# DIGITAL.net
KiCad netlist of a schematic drawn in Altium Designer
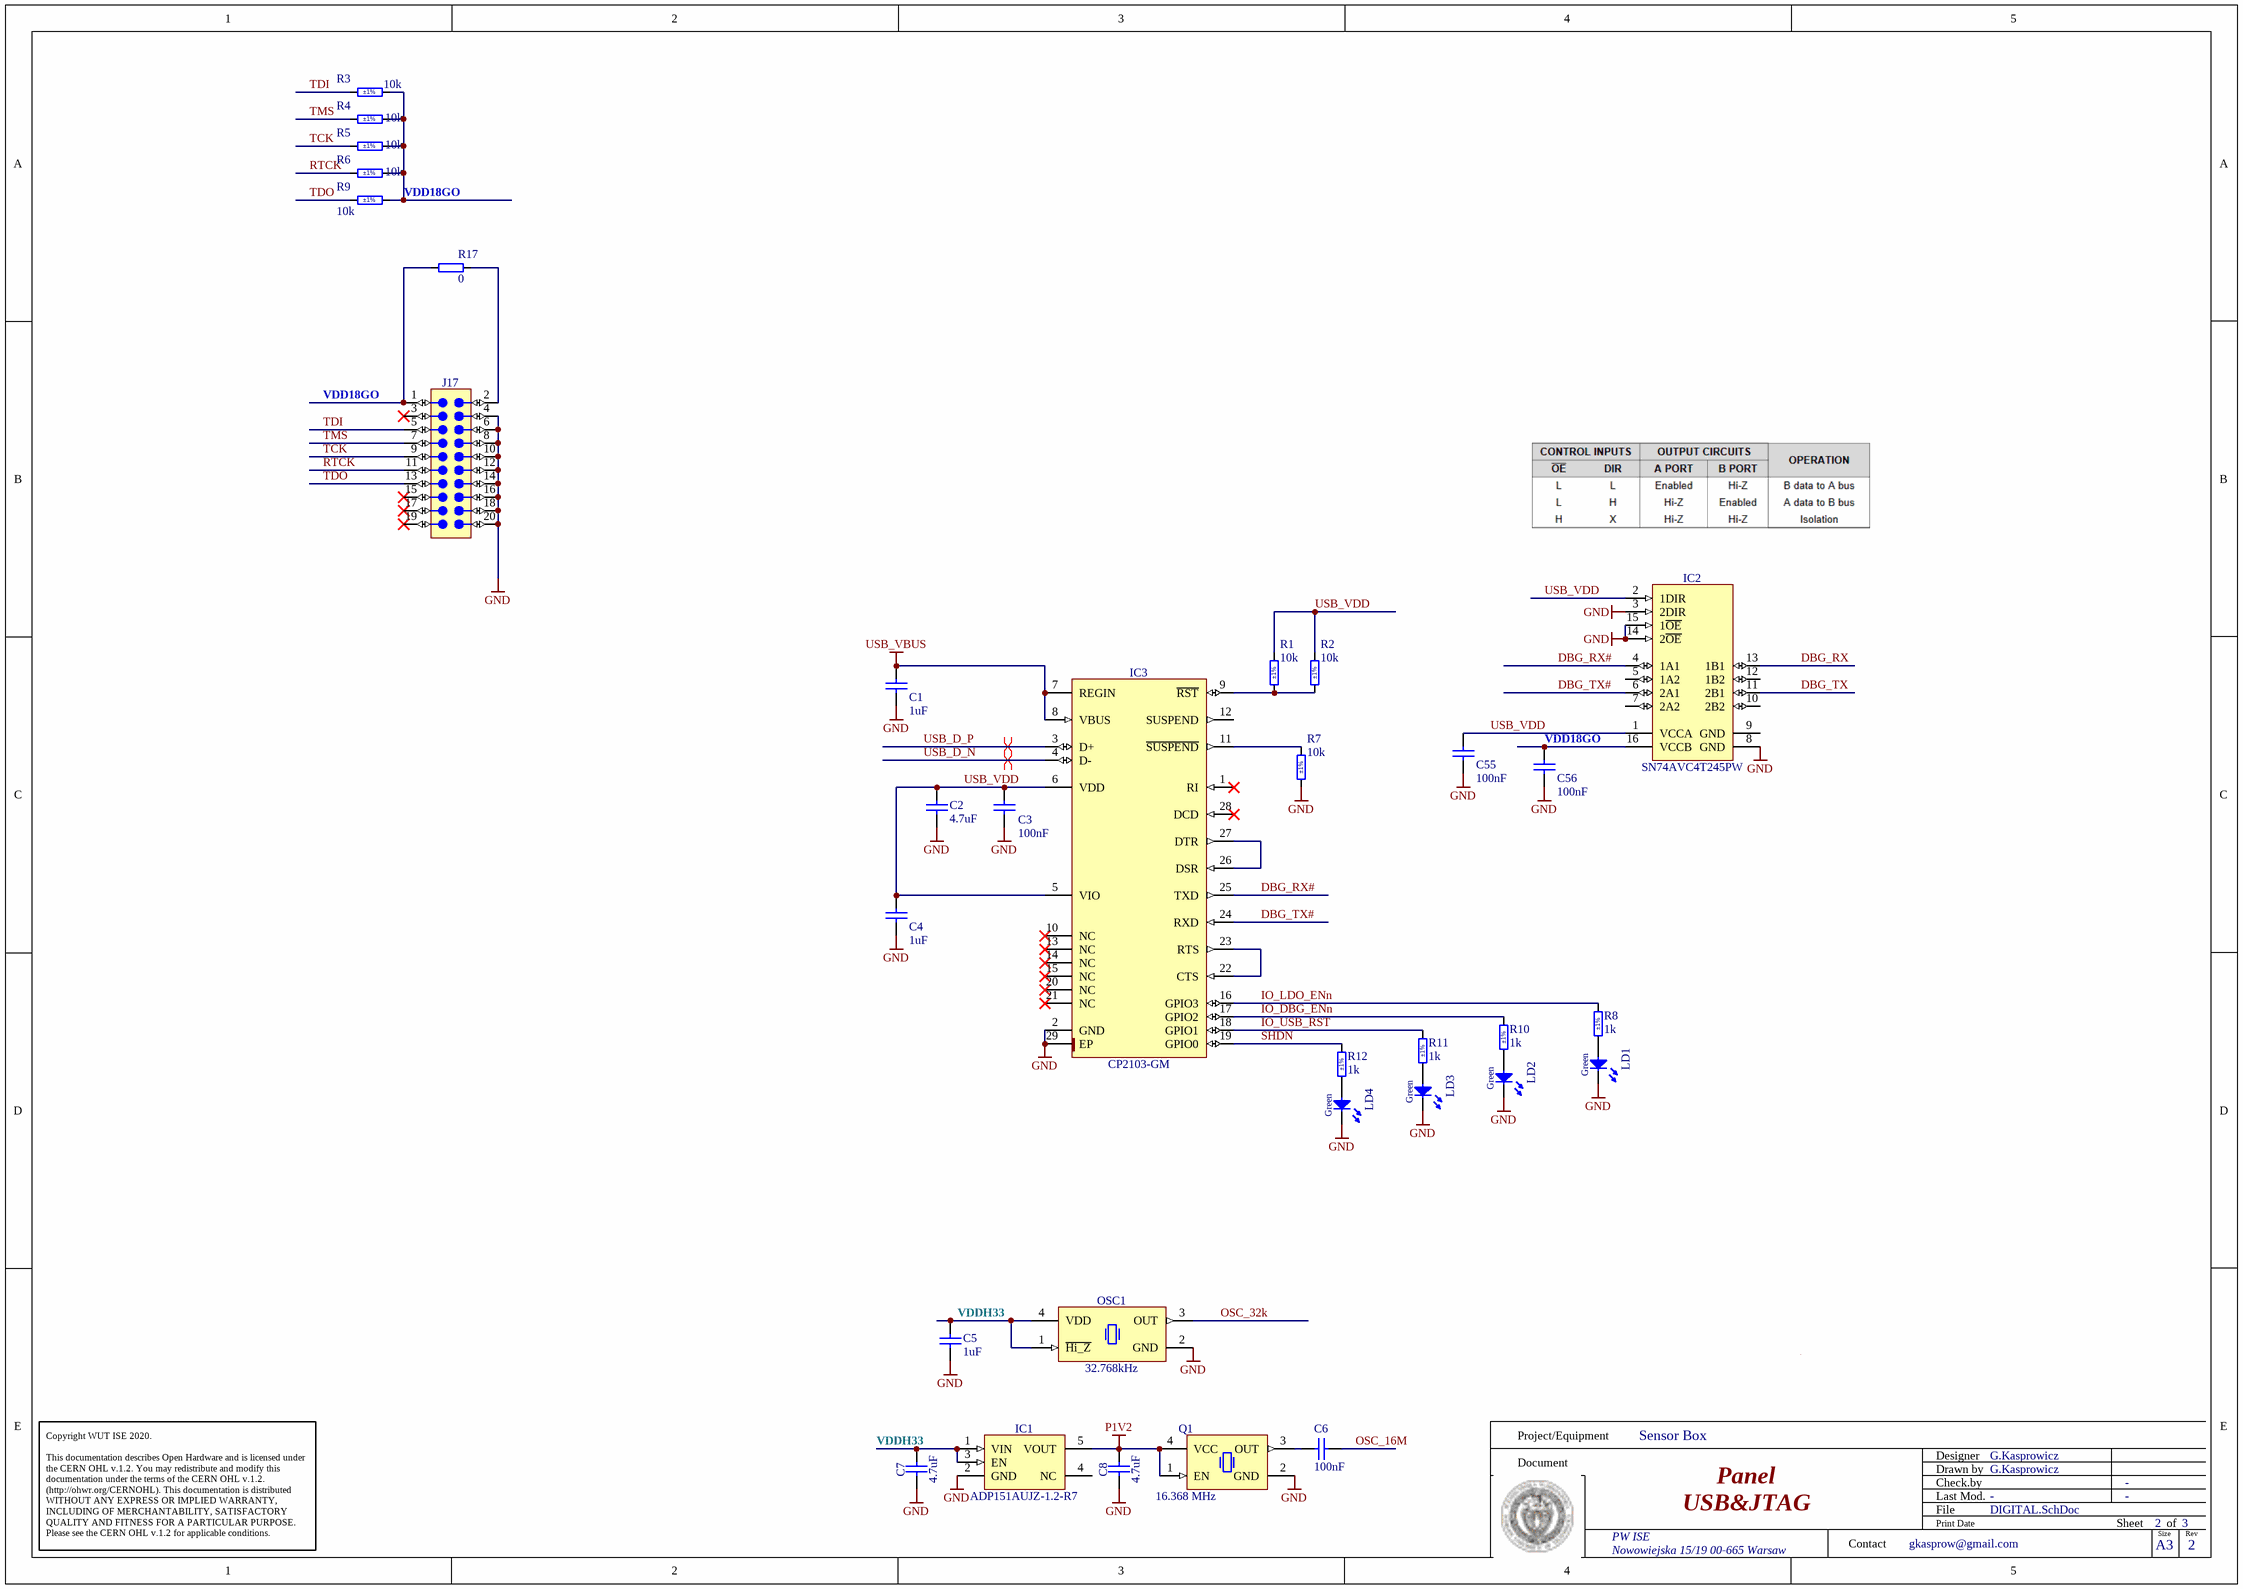
[diagram p0: DIGITAL.SchDoc]

(export (version "E")
  (design (tool "Eeschema 10.0.6"))
  (components
    (comp (ref "C1")
      (value "1uF")
      (footprint "CAPC1005X55N")
      (description "Non-polarised capacitor")
      (fields
        (field (name "PART NUMBER") "CC0402_1UF_16V_10%_X5R")
        (field (name "VOLTAGE") "16V")
        (field (name "AUTHOR") "CERN DEM JLC")
      )
      (libsource (lib "Capacitors") (part "Capacitor - non polarized"))
    )
    (comp (ref "C2")
      (value "4.7uF")
      (footprint "CAPC1005X55N")
      (description "Non-polarised capacitor")
      (fields
        (field (name "PART NUMBER") "CC0402_4.7UF_10V_10%_X5R")
        (field (name "VOLTAGE") "10V")
        (field (name "AUTHOR") "CERN DEM BC")
      )
      (libsource (lib "Capacitors") (part "Capacitor - non polarized"))
    )
    (comp (ref "C3")
      (value "100nF")
      (footprint "CAPC1005X55N")
      (description "Non-polarised capacitor")
      (fields
        (field (name "PART NUMBER") "CC0402_100NF_16V_10%_X5R")
        (field (name "VOLTAGE") "16V")
        (field (name "AUTHOR") "CERN DEM JLC")
      )
      (libsource (lib "Capacitors") (part "Capacitor - non polarized"))
    )
    (comp (ref "C4")
      (value "1uF")
      (footprint "CAPC1005X55N")
      (description "Non-polarised capacitor")
      (fields
        (field (name "PART NUMBER") "CC0402_1UF_16V_10%_X5R")
        (field (name "VOLTAGE") "16V")
        (field (name "AUTHOR") "CERN DEM JLC")
      )
      (libsource (lib "Capacitors") (part "Capacitor - non polarized"))
    )
    (comp (ref "C5")
      (value "1uF")
      (footprint "CAPC1005X55N")
      (description "Non-polarised capacitor")
      (fields
        (field (name "PART NUMBER") "CC0402_1UF_16V_10%_X5R")
        (field (name "VOLTAGE") "16V")
        (field (name "AUTHOR") "CERN DEM JLC")
      )
      (libsource (lib "Capacitors") (part "Capacitor - non polarized"))
    )
    (comp (ref "C6")
      (value "100nF")
      (footprint "CAPC1005X55N")
      (description "Non-polarised capacitor")
      (fields
        (field (name "PART NUMBER") "CC0402_100NF_16V_10%_X5R")
        (field (name "VOLTAGE") "16V")
        (field (name "AUTHOR") "CERN DEM JLC")
      )
      (libsource (lib "Capacitors") (part "Capacitor - non polarized"))
    )
    (comp (ref "C7")
      (value "4.7uF")
      (footprint "CAPC1005X55N")
      (description "Non-polarised capacitor")
      (fields
        (field (name "PART NUMBER") "CC0402_4.7UF_10V_10%_X5R")
        (field (name "VOLTAGE") "10V")
        (field (name "AUTHOR") "CERN DEM BC")
      )
      (libsource (lib "Capacitors") (part "Capacitor - non polarized"))
    )
    (comp (ref "C8")
      (value "4.7uF")
      (footprint "CAPC1005X55N")
      (description "Non-polarised capacitor")
      (fields
        (field (name "PART NUMBER") "CC0402_4.7UF_10V_10%_X5R")
        (field (name "VOLTAGE") "10V")
        (field (name "AUTHOR") "CERN DEM BC")
      )
      (libsource (lib "Capacitors") (part "Capacitor - non polarized"))
    )
    (comp (ref "C55")
      (value "100nF")
      (footprint "CAPC1005X55N")
      (description "Non-polarised capacitor")
      (fields
        (field (name "PART NUMBER") "CC0402_100NF_16V_10%_X5R")
        (field (name "VOLTAGE") "16V")
        (field (name "AUTHOR") "CERN DEM JLC")
      )
      (libsource (lib "Capacitors") (part "Capacitor - non polarized"))
    )
    (comp (ref "C56")
      (value "100nF")
      (footprint "CAPC1005X55N")
      (description "Non-polarised capacitor")
      (fields
        (field (name "PART NUMBER") "CC0402_100NF_16V_10%_X5R")
        (field (name "VOLTAGE") "16V")
        (field (name "AUTHOR") "CERN DEM JLC")
      )
      (libsource (lib "Capacitors") (part "Capacitor - non polarized"))
    )
    (comp (ref "IC1")
      (value "ADP151AUJZ-1.2-R7")
      (footprint "SOT95P280X90-5N")
      (description "Ultralow Noise, 200 mA CMOS Linear Regulator")
      (fields (field (name "MANUFACTURER") "ANALOG DEVICES") (field (name "AUTHOR") "CERN DEM JLC"))
      (libsource (lib "ICs And Semiconductors") (part "ADP151AUJZ"))
    )
    (comp (ref "IC2")
      (value "SN74AVC4T245PW")
      (footprint "SOP65P640X120-16N")
      (description "4-Bit Dual-Supply Bus Transceiver with Configurable Voltage Translation and 3-State Output")
      (fields (field (name "MANUFACTURER") "TEXAS INSTRUMENTS") (field (name "AUTHOR") "CERN DEM JLC"))
      (libsource (lib "ICs And Semiconductors") (part "744T245"))
    )
    (comp (ref "IC3")
      (value "CP2103-GM")
      (footprint "QFN50P500X500X100-29N-S335")
      (description "Single-Chip USB to UART Bridge")
      (fields (field (name "MANUFACTURER") "SILICON LABS") (field (name "AUTHOR") "CERN DEM JLC"))
      (libsource (lib "ICs And Semiconductors") (part "CP2103-GM"))
    )
    (comp (ref "J17")
      (value "Header 20")
      (footprint "SAMTEC_MTLW-110-07-L-D-250")
      (description "Connector 20 Male")
      (fields
        (field (name "PART NUMBER") "SAMTEC_MTLW-110-07-L-D-250")
        (field (name "MANUFACTURER") "SAMTEC")
        (field (name "AUTHOR") "CERN DEM JLC")
      )
      (libsource (lib "Connectors") (part "Connector 20 Male"))
    )
    (comp (ref "LD1")
      (value "Green")
      (footprint "LED_KINGBRIGHT_KP-1608CGCK")
      (description "LED Green 1C 2A")
      (fields
        (field (name "PART NUMBER") "LED_KINGBRIGHT_KP-1608CGCK")
        (field (name "MANUFACTURER") "KINGBRIGHT")
        (field (name "AUTHOR") "CERN DEM HF")
      )
      (libsource (lib "ICs And Semiconductors") (part "LED Green 1C 2A"))
    )
    (comp (ref "LD2")
      (value "Green")
      (footprint "LED_KINGBRIGHT_KP-1608CGCK")
      (description "LED Green 1C 2A")
      (fields
        (field (name "PART NUMBER") "LED_KINGBRIGHT_KP-1608CGCK")
        (field (name "MANUFACTURER") "KINGBRIGHT")
        (field (name "AUTHOR") "CERN DEM HF")
      )
      (libsource (lib "ICs And Semiconductors") (part "LED Green 1C 2A"))
    )
    (comp (ref "LD3")
      (value "Green")
      (footprint "LED_KINGBRIGHT_KP-1608CGCK")
      (description "LED Green 1C 2A")
      (fields
        (field (name "PART NUMBER") "LED_KINGBRIGHT_KP-1608CGCK")
        (field (name "MANUFACTURER") "KINGBRIGHT")
        (field (name "AUTHOR") "CERN DEM HF")
      )
      (libsource (lib "ICs And Semiconductors") (part "LED Green 1C 2A"))
    )
    (comp (ref "LD4")
      (value "Green")
      (footprint "LED_KINGBRIGHT_KP-1608CGCK")
      (description "LED Green 1C 2A")
      (fields
        (field (name "PART NUMBER") "LED_KINGBRIGHT_KP-1608CGCK")
        (field (name "MANUFACTURER") "KINGBRIGHT")
        (field (name "AUTHOR") "CERN DEM HF")
      )
      (libsource (lib "ICs And Semiconductors") (part "LED Green 1C 2A"))
    )
    (comp (ref "OSC1")
      (value "32.768kHz")
      (footprint "OSC_ABRACON_ASE")
      (description "Oscillator 32.768KHZ 25PPM 3.3V 3.2 x 2.5 x 1.2mm")
      (fields
        (field (name "PART NUMBER") "OSC_32.768kHz_ABRACON_ASEK-32.768KHz-LRT")
        (field (name "MANUFACTURER") "ABRACON")
        (field (name "AUTHOR") "GK")
      )
      (libsource (lib "Crystals_Oscillators") (part "OSC_32.768kHz_ABRACON_ASEK-32.768KHz-LRT"))
    )
    (comp (ref "Q1")
      (value "16.368 MHz")
      (footprint "XTAL_TXC_8Y")
      (description "2.0 x 1.6mm SMD TCXO 16.368 MHz 0.5ppm 1.2V")
      (fields
        (field (name "PART NUMBER") "OSC_16.368 MHz _IQD_LFTCXO077226Cutt")
        (field (name "MANUFACTURER") "IQD")
        (field (name "AUTHOR") "GK")
      )
      (libsource (lib "Crystals_Oscillators") (part "OSC_16.368 MHz _IQD_LFTCXO077226Cutt"))
    )
    (comp (ref "R1")
      (value "10k")
      (footprint "RESC1005X40N")
      (description "Resistor - 1%")
      (fields
        (field (name "TOLERANCE") "±1%")
        (field (name "PART NUMBER") "R0402_10K_1%_0.0625W_100PPM")
        (field (name "POWER") "0.0625W")
        (field (name "AUTHOR") "CERN DEM JLC")
      )
      (libsource (lib "Resistors") (part "Resistor - 1%"))
    )
    (comp (ref "R2")
      (value "10k")
      (footprint "RESC1005X40N")
      (description "Resistor - 1%")
      (fields
        (field (name "TOLERANCE") "±1%")
        (field (name "PART NUMBER") "R0402_10K_1%_0.0625W_100PPM")
        (field (name "POWER") "0.0625W")
        (field (name "AUTHOR") "CERN DEM JLC")
      )
      (libsource (lib "Resistors") (part "Resistor - 1%"))
    )
    (comp (ref "R3")
      (value "10k")
      (footprint "RESC1005X40N")
      (description "Resistor - 1%")
      (fields
        (field (name "TOLERANCE") "±1%")
        (field (name "PART NUMBER") "R0402_10K_1%_0.0625W_100PPM")
        (field (name "POWER") "0.0625W")
        (field (name "AUTHOR") "CERN DEM JLC")
      )
      (libsource (lib "Resistors") (part "Resistor - 1%"))
    )
    (comp (ref "R4")
      (value "10k")
      (footprint "RESC1005X40N")
      (description "Resistor - 1%")
      (fields
        (field (name "TOLERANCE") "±1%")
        (field (name "PART NUMBER") "R0402_10K_1%_0.0625W_100PPM")
        (field (name "POWER") "0.0625W")
        (field (name "AUTHOR") "CERN DEM JLC")
      )
      (libsource (lib "Resistors") (part "Resistor - 1%"))
    )
    (comp (ref "R5")
      (value "10k")
      (footprint "RESC1005X40N")
      (description "Resistor - 1%")
      (fields
        (field (name "TOLERANCE") "±1%")
        (field (name "PART NUMBER") "R0402_10K_1%_0.0625W_100PPM")
        (field (name "POWER") "0.0625W")
        (field (name "AUTHOR") "CERN DEM JLC")
      )
      (libsource (lib "Resistors") (part "Resistor - 1%"))
    )
    (comp (ref "R6")
      (value "10k")
      (footprint "RESC1005X40N")
      (description "Resistor - 1%")
      (fields
        (field (name "TOLERANCE") "±1%")
        (field (name "PART NUMBER") "R0402_10K_1%_0.0625W_100PPM")
        (field (name "POWER") "0.0625W")
        (field (name "AUTHOR") "CERN DEM JLC")
      )
      (libsource (lib "Resistors") (part "Resistor - 1%"))
    )
    (comp (ref "R7")
      (value "10k")
      (footprint "RESC1005X40N")
      (description "Resistor - 1%")
      (fields
        (field (name "TOLERANCE") "±1%")
        (field (name "PART NUMBER") "R0402_10K_1%_0.0625W_100PPM")
        (field (name "POWER") "0.0625W")
        (field (name "AUTHOR") "CERN DEM JLC")
      )
      (libsource (lib "Resistors") (part "Resistor - 1%"))
    )
    (comp (ref "R8")
      (value "1k")
      (footprint "RESC1005X40N")
      (description "Resistor - 1%")
      (fields
        (field (name "TOLERANCE") "±1%")
        (field (name "PART NUMBER") "R0402_1K_1%_0.0625W_100PPM")
        (field (name "POWER") "0.0625W")
        (field (name "AUTHOR") "CERN DEM JLC")
      )
      (libsource (lib "Resistors") (part "Resistor - 1%"))
    )
    (comp (ref "R9")
      (value "10k")
      (footprint "RESC1005X40N")
      (description "Resistor - 1%")
      (fields
        (field (name "TOLERANCE") "±1%")
        (field (name "PART NUMBER") "R0402_10K_1%_0.0625W_100PPM")
        (field (name "POWER") "0.0625W")
        (field (name "AUTHOR") "CERN DEM JLC")
      )
      (libsource (lib "Resistors") (part "Resistor - 1%"))
    )
    (comp (ref "R10")
      (value "1k")
      (footprint "RESC1005X40N")
      (description "Resistor - 1%")
      (fields
        (field (name "TOLERANCE") "±1%")
        (field (name "PART NUMBER") "R0402_1K_1%_0.0625W_100PPM")
        (field (name "POWER") "0.0625W")
        (field (name "AUTHOR") "CERN DEM JLC")
      )
      (libsource (lib "Resistors") (part "Resistor - 1%"))
    )
    (comp (ref "R11")
      (value "1k")
      (footprint "RESC1005X40N")
      (description "Resistor - 1%")
      (fields
        (field (name "TOLERANCE") "±1%")
        (field (name "PART NUMBER") "R0402_1K_1%_0.0625W_100PPM")
        (field (name "POWER") "0.0625W")
        (field (name "AUTHOR") "CERN DEM JLC")
      )
      (libsource (lib "Resistors") (part "Resistor - 1%"))
    )
    (comp (ref "R12")
      (value "1k")
      (footprint "RESC1005X40N")
      (description "Resistor - 1%")
      (fields
        (field (name "TOLERANCE") "±1%")
        (field (name "PART NUMBER") "R0402_1K_1%_0.0625W_100PPM")
        (field (name "POWER") "0.0625W")
        (field (name "AUTHOR") "CERN DEM JLC")
      )
      (libsource (lib "Resistors") (part "Resistor - 1%"))
    )
    (comp (ref "R17")
      (value "0")
      (footprint "RESC1005X40N")
      (description "Resistor")
      (fields
        (field (name "PART NUMBER") "R0402_0R_JUMPER")
        (field (name "MANUFACTURER") "GENERIC")
        (field (name "AUTHOR") "CERN DEM JLC")
      )
      (libsource (lib "Resistors") (part "Resistor"))
    )
  )
  (nets
    (net (code "1") (name "/DBG_RX") (class "Default")
      (node (ref "IC2") (pin "13") (pinfunction "1B1_13") (pintype "bidirectional"))
    )
    (net (code "2") (name "/DBG_RX#") (class "Default")
      (node (ref "IC2") (pin "4") (pinfunction "1A1_4") (pintype "bidirectional"))
      (node (ref "IC3") (pin "25") (pinfunction "TXD_25") (pintype "output"))
    )
    (net (code "3") (name "/DBG_TX") (class "Default")
      (node (ref "IC2") (pin "11") (pinfunction "2B1_11") (pintype "bidirectional"))
    )
    (net (code "4") (name "/DBG_TX#") (class "Default")
      (node (ref "IC2") (pin "6") (pinfunction "2A1_6") (pintype "bidirectional"))
      (node (ref "IC3") (pin "24") (pinfunction "RXD_24") (pintype "input"))
    )
    (net (code "5") (name "/IO_DBG_ENn") (class "Default")
      (node (ref "IC3") (pin "17") (pinfunction "GPIO2_17") (pintype "bidirectional"))
      (node (ref "R10") (pin "2") (pinfunction "2_2") (pintype "passive"))
    )
    (net (code "6") (name "/IO_LDO_ENn") (class "Default")
      (node (ref "IC3") (pin "16") (pinfunction "GPIO3_16") (pintype "bidirectional"))
      (node (ref "R8") (pin "2") (pinfunction "2_2") (pintype "passive"))
    )
    (net (code "7") (name "/IO_USB_RST") (class "Default")
      (node (ref "IC3") (pin "18") (pinfunction "GPIO1_18") (pintype "bidirectional"))
      (node (ref "R11") (pin "2") (pinfunction "2_2") (pintype "passive"))
    )
    (net (code "8") (name "/OSC_16M") (class "Default")
      (node (ref "C6") (pin "2") (pinfunction "2_2") (pintype "passive"))
    )
    (net (code "9") (name "/OSC_32k") (class "Default")
      (node (ref "OSC1") (pin "3") (pinfunction "OUT_3") (pintype "output"))
    )
    (net (code "10") (name "/RTCK") (class "Default")
      (node (ref "J17") (pin "11") (pinfunction "11_11") (pintype "bidirectional"))
      (node (ref "R6") (pin "1") (pinfunction "1_1") (pintype "passive"))
    )
    (net (code "11") (name "/SHDN") (class "Default")
      (node (ref "IC3") (pin "19") (pinfunction "GPIO0_19") (pintype "bidirectional"))
      (node (ref "R12") (pin "2") (pinfunction "2_2") (pintype "passive"))
    )
    (net (code "12") (name "/TCK") (class "Default")
      (node (ref "J17") (pin "9") (pinfunction "9_9") (pintype "bidirectional"))
      (node (ref "R5") (pin "1") (pinfunction "1_1") (pintype "passive"))
    )
    (net (code "13") (name "/TDI") (class "Default")
      (node (ref "J17") (pin "5") (pinfunction "5_5") (pintype "bidirectional"))
      (node (ref "R3") (pin "1") (pinfunction "1_1") (pintype "passive"))
    )
    (net (code "14") (name "/TDO") (class "Default")
      (node (ref "J17") (pin "13") (pinfunction "13_13") (pintype "bidirectional"))
      (node (ref "R9") (pin "1") (pinfunction "1_1") (pintype "passive"))
    )
    (net (code "15") (name "/TMS") (class "Default")
      (node (ref "J17") (pin "7") (pinfunction "7_7") (pintype "bidirectional"))
      (node (ref "R4") (pin "1") (pinfunction "1_1") (pintype "passive"))
    )
    (net (code "16") (name "/USB_D_N") (class "Default")
      (node (ref "IC3") (pin "4") (pinfunction "D-_4") (pintype "bidirectional"))
    )
    (net (code "17") (name "/USB_D_P") (class "Default")
      (node (ref "IC3") (pin "3") (pinfunction "D+_3") (pintype "bidirectional"))
    )
    (net (code "18") (name "/USB_VDD") (class "Default")
      (node (ref "C2") (pin "1") (pinfunction "1_1") (pintype "passive"))
      (node (ref "C3") (pin "2") (pinfunction "2_2") (pintype "passive"))
      (node (ref "C4") (pin "2") (pinfunction "2_2") (pintype "passive"))
      (node (ref "C55") (pin "2") (pinfunction "2_2") (pintype "passive"))
      (node (ref "IC2") (pin "1") (pinfunction "VCCA_1") (pintype "power_in"))
      (node (ref "IC2") (pin "2") (pinfunction "1DIR_2") (pintype "input"))
      (node (ref "IC3") (pin "5") (pinfunction "VIO_5") (pintype "power_in"))
      (node (ref "IC3") (pin "6") (pinfunction "VDD_6") (pintype "power_in"))
      (node (ref "R1") (pin "1") (pinfunction "1_1") (pintype "passive"))
      (node (ref "R2") (pin "1") (pinfunction "1_1") (pintype "passive"))
    )
    (net (code "19") (name "/VDD18GO") (class "Default")
      (node (ref "C56") (pin "2") (pinfunction "2_2") (pintype "passive"))
      (node (ref "IC2") (pin "16") (pinfunction "VCCB_16") (pintype "power_in"))
      (node (ref "J17") (pin "1") (pinfunction "1_1") (pintype "bidirectional"))
      (node (ref "R17") (pin "2") (pinfunction "2_2") (pintype "passive"))
      (node (ref "R3") (pin "2") (pinfunction "2_2") (pintype "passive"))
      (node (ref "R4") (pin "2") (pinfunction "2_2") (pintype "passive"))
      (node (ref "R5") (pin "2") (pinfunction "2_2") (pintype "passive"))
      (node (ref "R6") (pin "2") (pinfunction "2_2") (pintype "passive"))
      (node (ref "R9") (pin "2") (pinfunction "2_2") (pintype "passive"))
    )
    (net (code "20") (name "/VDDH33") (class "Default")
      (node (ref "C5") (pin "1") (pinfunction "1_1") (pintype "passive"))
      (node (ref "C7") (pin "2") (pinfunction "2_2") (pintype "passive"))
      (node (ref "IC1") (pin "1") (pinfunction "VIN_1") (pintype "input"))
      (node (ref "IC1") (pin "3") (pinfunction "EN_3") (pintype "input"))
      (node (ref "OSC1") (pin "1") (pinfunction "~{Hi_Z}_1") (pintype "input"))
      (node (ref "OSC1") (pin "4") (pinfunction "VDD_4") (pintype "power_in"))
    )
    (net (code "21") (name "GND") (class "Default")
      (node (ref "C1") (pin "1") (pinfunction "1_1") (pintype "passive"))
      (node (ref "C2") (pin "2") (pinfunction "2_2") (pintype "passive"))
      (node (ref "C3") (pin "1") (pinfunction "1_1") (pintype "passive"))
      (node (ref "C4") (pin "1") (pinfunction "1_1") (pintype "passive"))
      (node (ref "C5") (pin "2") (pinfunction "2_2") (pintype "passive"))
      (node (ref "C55") (pin "1") (pinfunction "1_1") (pintype "passive"))
      (node (ref "C56") (pin "1") (pinfunction "1_1") (pintype "passive"))
      (node (ref "C7") (pin "1") (pinfunction "1_1") (pintype "passive"))
      (node (ref "C8") (pin "1") (pinfunction "1_1") (pintype "passive"))
      (node (ref "IC1") (pin "2") (pinfunction "GND_2") (pintype "power_in"))
      (node (ref "IC2") (pin "14") (pinfunction "2~{OE}_14") (pintype "input"))
      (node (ref "IC2") (pin "15") (pinfunction "1~{OE}_15") (pintype "input"))
      (node (ref "IC2") (pin "3") (pinfunction "2DIR_3") (pintype "input"))
      (node (ref "IC2") (pin "8") (pinfunction "GND_8") (pintype "power_in"))
      (node (ref "IC3") (pin "2") (pinfunction "GND_2") (pintype "power_in"))
      (node (ref "IC3") (pin "29") (pinfunction "EP_29") (pintype "power_in"))
      (node (ref "J17") (pin "10") (pinfunction "10_10") (pintype "bidirectional"))
      (node (ref "J17") (pin "12") (pinfunction "12_12") (pintype "bidirectional"))
      (node (ref "J17") (pin "14") (pinfunction "14_14") (pintype "bidirectional"))
      (node (ref "J17") (pin "16") (pinfunction "16_16") (pintype "bidirectional"))
      (node (ref "J17") (pin "18") (pinfunction "18_18") (pintype "bidirectional"))
      (node (ref "J17") (pin "20") (pinfunction "20_20") (pintype "bidirectional"))
      (node (ref "J17") (pin "4") (pinfunction "4_4") (pintype "bidirectional"))
      (node (ref "J17") (pin "6") (pinfunction "6_6") (pintype "bidirectional"))
      (node (ref "J17") (pin "8") (pinfunction "8_8") (pintype "bidirectional"))
      (node (ref "LD1") (pin "1") (pinfunction "C_1") (pintype "passive"))
      (node (ref "LD2") (pin "1") (pinfunction "C_1") (pintype "passive"))
      (node (ref "LD3") (pin "1") (pinfunction "C_1") (pintype "passive"))
      (node (ref "LD4") (pin "1") (pinfunction "C_1") (pintype "passive"))
      (node (ref "OSC1") (pin "2") (pinfunction "GND_2") (pintype "power_in"))
      (node (ref "Q1") (pin "2") (pinfunction "GND_2") (pintype "power_in"))
      (node (ref "R7") (pin "2") (pinfunction "2_2") (pintype "passive"))
    )
    (net (code "22") (name "Net-(IC3-CTS)") (class "Default")
      (node (ref "IC3") (pin "22") (pinfunction "CTS_22") (pintype "input"))
      (node (ref "IC3") (pin "23") (pinfunction "RTS_23") (pintype "output"))
    )
    (net (code "23") (name "Net-(IC3-DSR)") (class "Default")
      (node (ref "IC3") (pin "26") (pinfunction "DSR_26") (pintype "input"))
      (node (ref "IC3") (pin "27") (pinfunction "DTR_27") (pintype "output"))
    )
    (net (code "24") (name "Net-(IC3-~{RST})") (class "Default")
      (node (ref "IC3") (pin "9") (pinfunction "~{RST}_9") (pintype "bidirectional"))
      (node (ref "R1") (pin "2") (pinfunction "2_2") (pintype "passive"))
      (node (ref "R2") (pin "2") (pinfunction "2_2") (pintype "passive"))
    )
    (net (code "25") (name "Net-(IC3-~{SUSPEND})") (class "Default")
      (node (ref "IC3") (pin "11") (pinfunction "~{SUSPEND}_11") (pintype "output"))
      (node (ref "R7") (pin "1") (pinfunction "1_1") (pintype "passive"))
    )
    (net (code "26") (name "Net-(J17-Pad2)") (class "Default")
      (node (ref "J17") (pin "2") (pinfunction "2_2") (pintype "bidirectional"))
      (node (ref "R17") (pin "1") (pinfunction "1_1") (pintype "passive"))
    )
    (net (code "27") (name "Net-(LD1-A)") (class "Default")
      (node (ref "LD1") (pin "2") (pinfunction "A_2") (pintype "passive"))
      (node (ref "R8") (pin "1") (pinfunction "1_1") (pintype "passive"))
    )
    (net (code "28") (name "Net-(LD2-A)") (class "Default")
      (node (ref "LD2") (pin "2") (pinfunction "A_2") (pintype "passive"))
      (node (ref "R10") (pin "1") (pinfunction "1_1") (pintype "passive"))
    )
    (net (code "29") (name "Net-(LD3-A)") (class "Default")
      (node (ref "LD3") (pin "2") (pinfunction "A_2") (pintype "passive"))
      (node (ref "R11") (pin "1") (pinfunction "1_1") (pintype "passive"))
    )
    (net (code "30") (name "Net-(LD4-A)") (class "Default")
      (node (ref "LD4") (pin "2") (pinfunction "A_2") (pintype "passive"))
      (node (ref "R12") (pin "1") (pinfunction "1_1") (pintype "passive"))
    )
    (net (code "31") (name "Net-(Q1-OUT)") (class "Default")
      (node (ref "C6") (pin "1") (pinfunction "1_1") (pintype "passive"))
      (node (ref "Q1") (pin "3") (pinfunction "OUT_3") (pintype "output"))
    )
    (net (code "32") (name "P1V2") (class "Default")
      (node (ref "C8") (pin "2") (pinfunction "2_2") (pintype "passive"))
      (node (ref "IC1") (pin "5") (pinfunction "VOUT_5") (pintype "power_in"))
      (node (ref "Q1") (pin "1") (pinfunction "EN_1") (pintype "input"))
      (node (ref "Q1") (pin "4") (pinfunction "VCC_4") (pintype "power_in"))
    )
    (net (code "33") (name "USB_VBUS") (class "Default")
      (node (ref "C1") (pin "2") (pinfunction "2_2") (pintype "passive"))
      (node (ref "IC3") (pin "7") (pinfunction "REGIN_7") (pintype "power_in"))
      (node (ref "IC3") (pin "8") (pinfunction "VBUS_8") (pintype "input"))
    )
    (net (code "34") (name "unconnected-(IC1-NC-Pad4)") (class "Default")
      (node (ref "IC1") (pin "4") (pinfunction "NC_4") (pintype "passive"))
    )
    (net (code "35") (name "unconnected-(IC2-1A2-Pad5)") (class "Default")
      (node (ref "IC2") (pin "5") (pinfunction "1A2_5") (pintype "bidirectional"))
    )
    (net (code "36") (name "unconnected-(IC2-1B2-Pad12)") (class "Default")
      (node (ref "IC2") (pin "12") (pinfunction "1B2_12") (pintype "bidirectional"))
    )
    (net (code "37") (name "unconnected-(IC2-2A2-Pad7)") (class "Default")
      (node (ref "IC2") (pin "7") (pinfunction "2A2_7") (pintype "bidirectional"))
    )
    (net (code "38") (name "unconnected-(IC2-2B2-Pad10)") (class "Default")
      (node (ref "IC2") (pin "10") (pinfunction "2B2_10") (pintype "bidirectional"))
    )
    (net (code "39") (name "unconnected-(IC2-GND-Pad9)") (class "Default")
      (node (ref "IC2") (pin "9") (pinfunction "GND_9") (pintype "power_in"))
    )
    (net (code "40") (name "unconnected-(IC3-DCD-Pad28)") (class "Default")
      (node (ref "IC3") (pin "28") (pinfunction "DCD_28") (pintype "input+no_connect"))
    )
    (net (code "41") (name "unconnected-(IC3-NC-Pad10)") (class "Default")
      (node (ref "IC3") (pin "10") (pinfunction "NC_10") (pintype "passive+no_connect"))
    )
    (net (code "42") (name "unconnected-(IC3-NC-Pad13)") (class "Default")
      (node (ref "IC3") (pin "13") (pinfunction "NC_13") (pintype "passive+no_connect"))
    )
    (net (code "43") (name "unconnected-(IC3-NC-Pad14)") (class "Default")
      (node (ref "IC3") (pin "14") (pinfunction "NC_14") (pintype "passive+no_connect"))
    )
    (net (code "44") (name "unconnected-(IC3-NC-Pad15)") (class "Default")
      (node (ref "IC3") (pin "15") (pinfunction "NC_15") (pintype "passive+no_connect"))
    )
    (net (code "45") (name "unconnected-(IC3-NC-Pad20)") (class "Default")
      (node (ref "IC3") (pin "20") (pinfunction "NC_20") (pintype "passive+no_connect"))
    )
    (net (code "46") (name "unconnected-(IC3-NC-Pad21)") (class "Default")
      (node (ref "IC3") (pin "21") (pinfunction "NC_21") (pintype "passive+no_connect"))
    )
    (net (code "47") (name "unconnected-(IC3-RI-Pad1)") (class "Default")
      (node (ref "IC3") (pin "1") (pinfunction "RI_1") (pintype "input+no_connect"))
    )
    (net (code "48") (name "unconnected-(IC3-SUSPEND-Pad12)") (class "Default")
      (node (ref "IC3") (pin "12") (pinfunction "SUSPEND_12") (pintype "output"))
    )
    (net (code "49") (name "unconnected-(J17-Pad3)") (class "Default")
      (node (ref "J17") (pin "3") (pinfunction "3_3") (pintype "bidirectional+no_connect"))
    )
    (net (code "50") (name "unconnected-(J17-Pad15)") (class "Default")
      (node (ref "J17") (pin "15") (pinfunction "15_15") (pintype "bidirectional+no_connect"))
    )
    (net (code "51") (name "unconnected-(J17-Pad17)") (class "Default")
      (node (ref "J17") (pin "17") (pinfunction "17_17") (pintype "bidirectional+no_connect"))
    )
    (net (code "52") (name "unconnected-(J17-Pad19)") (class "Default")
      (node (ref "J17") (pin "19") (pinfunction "19_19") (pintype "bidirectional+no_connect"))
    )
  )
)
